# TopLevel.net
KiCad netlist of a schematic drawn in Altium Designer
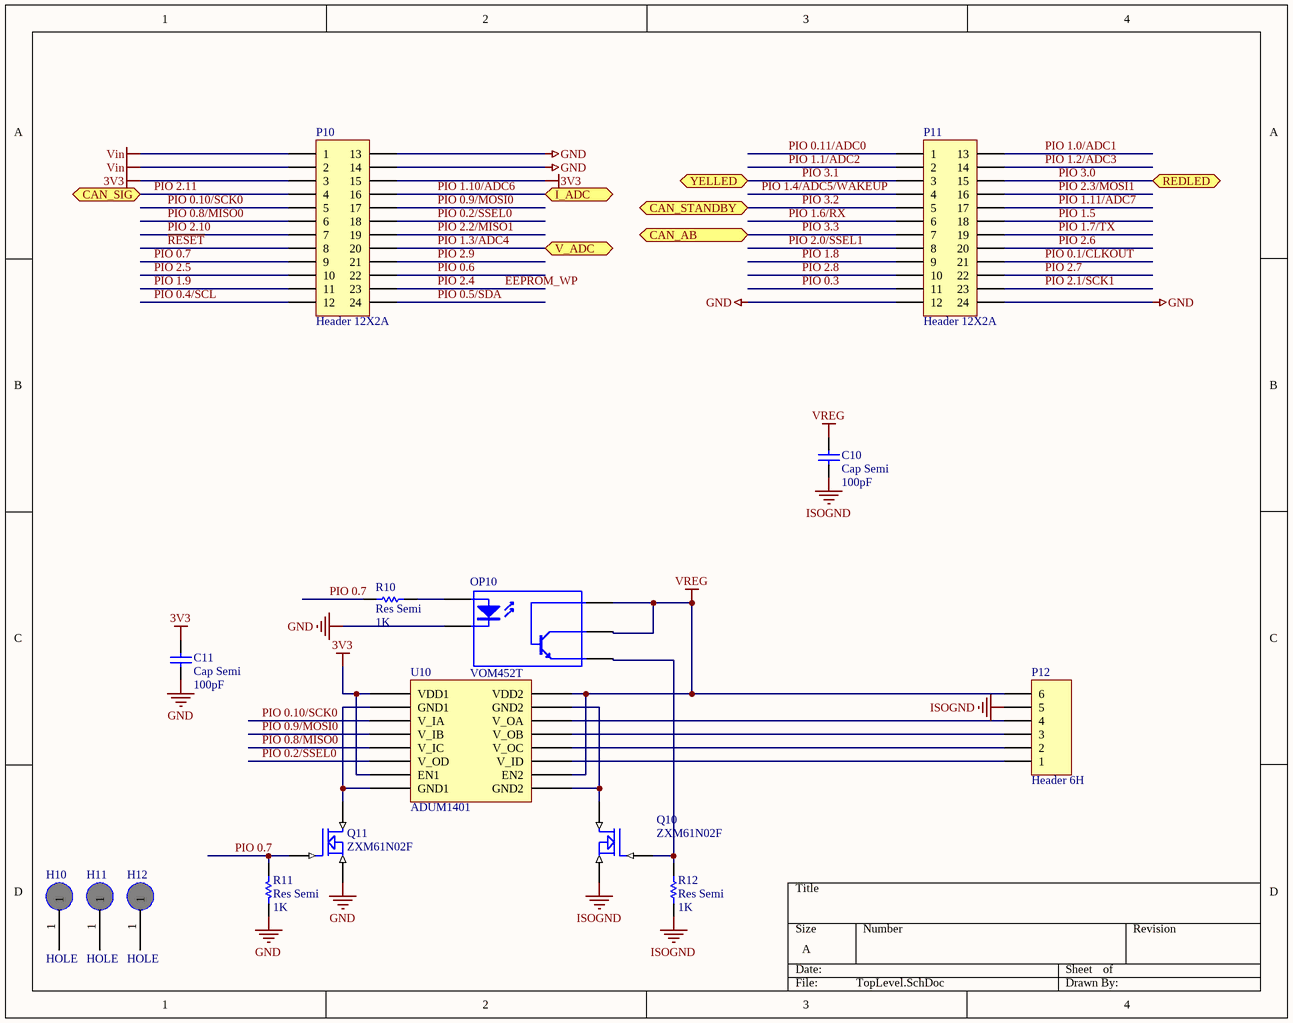
[diagram p0: TopLevel.SchDoc]

(export (version "E")
  (design (tool "Eeschema 10.0.6"))
  (components
    (comp (ref "C10")
      (value "Cap Semi")
      (footprint "1608[0603]")
      (description "Capacitor (Semiconductor SIM Model)")
      (fields (field (name "ALTIUM_VALUE") "100pF") (field (name "PUBLISHER") "Altium Limited"))
      (libsource (lib "Miscellaneous Devices") (part "Cap Semi"))
    )
    (comp (ref "C11")
      (value "Cap Semi")
      (footprint "1608[0603]")
      (description "Capacitor (Semiconductor SIM Model)")
      (fields (field (name "ALTIUM_VALUE") "100pF") (field (name "PUBLISHER") "Altium Limited"))
      (libsource (lib "Miscellaneous Devices") (part "Cap Semi"))
    )
    (comp (ref "H10")
      (value "HOLE")
      (footprint "M2.5")
      (description "Hole")
      (libsource (lib "Miscellaneous") (part "HOLE"))
    )
    (comp (ref "H11")
      (value "HOLE")
      (footprint "M2.5")
      (description "Hole")
      (libsource (lib "Miscellaneous") (part "HOLE"))
    )
    (comp (ref "H12")
      (value "HOLE")
      (footprint "M2.5")
      (description "Hole")
      (libsource (lib "Miscellaneous") (part "HOLE"))
    )
    (comp (ref "OP10") (value "VOM452T") (footprint "VOM452T") (libsource (lib "BMS") (part "VOM452T")))
    (comp (ref "P10")
      (value "Header 12X2A")
      (footprint "HDR2X12_CEN")
      (description "Header, 12-Pin, Dual row")
      (fields (field (name "PUBLISHER") "Altium Limited"))
      (libsource (lib "Miscellaneous Connectors") (part "Header 12X2A"))
    )
    (comp (ref "P11")
      (value "Header 12X2A")
      (footprint "HDR2X12_CEN")
      (description "Header, 12-Pin, Dual row")
      (fields (field (name "PUBLISHER") "Altium Limited"))
      (libsource (lib "Miscellaneous Connectors") (part "Header 12X2A"))
    )
    (comp (ref "P12")
      (value "Header 6H")
      (footprint "HDR1X6H")
      (description "Header, 6-Pin, Right Angle")
      (fields (field (name "PUBLISHER") "Altium Limited"))
      (libsource (lib "Miscellaneous Connectors") (part "Header 6H"))
    )
    (comp (ref "Q10")
      (value "ZXM61N02F")
      (footprint "SOT23-3")
      (description "1.7A, 20V N-Channel Enhancement mode FET")
      (libsource (lib "RCLDQ") (part "ZXM61N02F"))
    )
    (comp (ref "Q11")
      (value "ZXM61N02F")
      (footprint "SOT23-3")
      (description "1.7A, 20V N-Channel Enhancement mode FET")
      (libsource (lib "RCLDQ") (part "ZXM61N02F"))
    )
    (comp (ref "R10")
      (value "Res Semi")
      (footprint "0603")
      (description "Semiconductor Resistor")
      (fields (field (name "ALTIUM_VALUE") "1K") (field (name "PUBLISHER") "Altium Limited"))
      (libsource (lib "Miscellaneous Devices") (part "Res Semi"))
    )
    (comp (ref "R11")
      (value "Res Semi")
      (footprint "0603")
      (description "Semiconductor Resistor")
      (fields (field (name "ALTIUM_VALUE") "1K") (field (name "PUBLISHER") "Altium Limited"))
      (libsource (lib "Miscellaneous Devices") (part "Res Semi"))
    )
    (comp (ref "R12")
      (value "Res Semi")
      (footprint "0603")
      (description "Semiconductor Resistor")
      (fields (field (name "ALTIUM_VALUE") "1K") (field (name "PUBLISHER") "Altium Limited"))
      (libsource (lib "Miscellaneous Devices") (part "Res Semi"))
    )
    (comp (ref "U10") (value "ADUM1401") (footprint "SOIC_16_wide") (libsource (lib "BMS") (part "ADUM1401")))
  )
  (nets
    (net (code "1") (name "/EEPROM_WP") (class "Default")
      (node (ref "P10") (pin "23") (pinfunction "23_23") (pintype "passive"))
    )
    (net (code "2") (name "/PIO 0.1{slash}CLKOUT") (class "Default")
      (node (ref "P11") (pin "21") (pinfunction "21_21") (pintype "passive"))
    )
    (net (code "3") (name "/PIO 0.2{slash}SSEL0") (class "Default")
      (node (ref "P10") (pin "18") (pinfunction "18_18") (pintype "passive"))
      (node (ref "U10") (pin "6") (pinfunction "V_OD_6") (pintype "passive"))
    )
    (net (code "4") (name "/PIO 0.3") (class "Default")
      (node (ref "P11") (pin "11") (pinfunction "11_11") (pintype "passive"))
    )
    (net (code "5") (name "/PIO 0.4{slash}SCL") (class "Default")
      (node (ref "P10") (pin "12") (pinfunction "12_12") (pintype "passive"))
    )
    (net (code "6") (name "/PIO 0.5{slash}SDA") (class "Default")
      (node (ref "P10") (pin "24") (pinfunction "24_24") (pintype "passive"))
    )
    (net (code "7") (name "/PIO 0.6") (class "Default")
      (node (ref "P10") (pin "22") (pinfunction "22_22") (pintype "passive"))
    )
    (net (code "8") (name "/PIO 0.7") (class "Default")
      (node (ref "P10") (pin "9") (pinfunction "9_9") (pintype "passive"))
      (node (ref "Q11") (pin "1") (pinfunction "G_1") (pintype "input"))
      (node (ref "R10") (pin "2") (pinfunction "2_2") (pintype "passive"))
      (node (ref "R11") (pin "2") (pinfunction "2_2") (pintype "passive"))
    )
    (net (code "9") (name "/PIO 0.8{slash}MISO0") (class "Default")
      (node (ref "P10") (pin "6") (pinfunction "6_6") (pintype "passive"))
      (node (ref "U10") (pin "5") (pinfunction "V_IC_5") (pintype "passive"))
    )
    (net (code "10") (name "/PIO 0.9{slash}MOSI0") (class "Default")
      (node (ref "P10") (pin "17") (pinfunction "17_17") (pintype "passive"))
      (node (ref "U10") (pin "4") (pinfunction "V_IB_4") (pintype "passive"))
    )
    (net (code "11") (name "/PIO 0.10{slash}SCK0") (class "Default")
      (node (ref "P10") (pin "5") (pinfunction "5_5") (pintype "passive"))
      (node (ref "U10") (pin "3") (pinfunction "V_IA_3") (pintype "passive"))
    )
    (net (code "12") (name "/PIO 0.11{slash}ADC0") (class "Default")
      (node (ref "P11") (pin "1") (pinfunction "1_1") (pintype "passive"))
    )
    (net (code "13") (name "/PIO 1.0{slash}ADC1") (class "Default")
      (node (ref "P11") (pin "13") (pinfunction "13_13") (pintype "passive"))
    )
    (net (code "14") (name "/PIO 1.1{slash}ADC2") (class "Default")
      (node (ref "P11") (pin "2") (pinfunction "2_2") (pintype "passive"))
    )
    (net (code "15") (name "/PIO 1.2{slash}ADC3") (class "Default")
      (node (ref "P11") (pin "14") (pinfunction "14_14") (pintype "passive"))
    )
    (net (code "16") (name "/PIO 1.3{slash}ADC4") (class "Default")
      (node (ref "P10") (pin "20") (pinfunction "20_20") (pintype "passive"))
    )
    (net (code "17") (name "/PIO 1.4{slash}ADC5{slash}WAKEUP") (class "Default")
      (node (ref "P11") (pin "4") (pinfunction "4_4") (pintype "passive"))
    )
    (net (code "18") (name "/PIO 1.5") (class "Default")
      (node (ref "P11") (pin "18") (pinfunction "18_18") (pintype "passive"))
    )
    (net (code "19") (name "/PIO 1.6{slash}RX") (class "Default")
      (node (ref "P11") (pin "6") (pinfunction "6_6") (pintype "passive"))
    )
    (net (code "20") (name "/PIO 1.7{slash}TX") (class "Default")
      (node (ref "P11") (pin "19") (pinfunction "19_19") (pintype "passive"))
    )
    (net (code "21") (name "/PIO 1.8") (class "Default")
      (node (ref "P11") (pin "9") (pinfunction "9_9") (pintype "passive"))
    )
    (net (code "22") (name "/PIO 1.9") (class "Default")
      (node (ref "P10") (pin "11") (pinfunction "11_11") (pintype "passive"))
    )
    (net (code "23") (name "/PIO 1.10{slash}ADC6") (class "Default")
      (node (ref "P10") (pin "16") (pinfunction "16_16") (pintype "passive"))
    )
    (net (code "24") (name "/PIO 1.11{slash}ADC7") (class "Default")
      (node (ref "P11") (pin "17") (pinfunction "17_17") (pintype "passive"))
    )
    (net (code "25") (name "/PIO 2.0{slash}SSEL1") (class "Default")
      (node (ref "P11") (pin "8") (pinfunction "8_8") (pintype "passive"))
    )
    (net (code "26") (name "/PIO 2.1{slash}SCK1") (class "Default")
      (node (ref "P11") (pin "23") (pinfunction "23_23") (pintype "passive"))
    )
    (net (code "27") (name "/PIO 2.2{slash}MISO1") (class "Default")
      (node (ref "P10") (pin "19") (pinfunction "19_19") (pintype "passive"))
    )
    (net (code "28") (name "/PIO 2.3{slash}MOSI1") (class "Default")
      (node (ref "P11") (pin "16") (pinfunction "16_16") (pintype "passive"))
    )
    (net (code "29") (name "/PIO 2.5") (class "Default")
      (node (ref "P10") (pin "10") (pinfunction "10_10") (pintype "passive"))
    )
    (net (code "30") (name "/PIO 2.6") (class "Default")
      (node (ref "P11") (pin "20") (pinfunction "20_20") (pintype "passive"))
    )
    (net (code "31") (name "/PIO 2.7") (class "Default")
      (node (ref "P11") (pin "22") (pinfunction "22_22") (pintype "passive"))
    )
    (net (code "32") (name "/PIO 2.8") (class "Default")
      (node (ref "P11") (pin "10") (pinfunction "10_10") (pintype "passive"))
    )
    (net (code "33") (name "/PIO 2.9") (class "Default")
      (node (ref "P10") (pin "21") (pinfunction "21_21") (pintype "passive"))
    )
    (net (code "34") (name "/PIO 2.10") (class "Default")
      (node (ref "P10") (pin "7") (pinfunction "7_7") (pintype "passive"))
    )
    (net (code "35") (name "/PIO 2.11") (class "Default")
      (node (ref "P10") (pin "4") (pinfunction "4_4") (pintype "passive"))
    )
    (net (code "36") (name "/PIO 3.0") (class "Default")
      (node (ref "P11") (pin "15") (pinfunction "15_15") (pintype "passive"))
    )
    (net (code "37") (name "/PIO 3.1") (class "Default")
      (node (ref "P11") (pin "3") (pinfunction "3_3") (pintype "passive"))
    )
    (net (code "38") (name "/PIO 3.2") (class "Default")
      (node (ref "P11") (pin "5") (pinfunction "5_5") (pintype "passive"))
    )
    (net (code "39") (name "/PIO 3.3") (class "Default")
      (node (ref "P11") (pin "7") (pinfunction "7_7") (pintype "passive"))
    )
    (net (code "40") (name "/~{RESET}") (class "Default")
      (node (ref "P10") (pin "8") (pinfunction "8_8") (pintype "passive"))
    )
    (net (code "41") (name "3V3") (class "Default")
      (node (ref "C11") (pin "2") (pinfunction "2_2") (pintype "passive"))
      (node (ref "P10") (pin "15") (pinfunction "15_15") (pintype "passive"))
      (node (ref "P10") (pin "3") (pinfunction "3_3") (pintype "passive"))
      (node (ref "U10") (pin "1") (pinfunction "VDD1_1") (pintype "passive"))
      (node (ref "U10") (pin "7") (pinfunction "EN1_7") (pintype "passive"))
    )
    (net (code "42") (name "GND") (class "Default")
      (node (ref "C11") (pin "1") (pinfunction "1_1") (pintype "passive"))
      (node (ref "OP10") (pin "3") (pinfunction "K_3") (pintype "passive"))
      (node (ref "P10") (pin "13") (pinfunction "13_13") (pintype "passive"))
      (node (ref "P10") (pin "14") (pinfunction "14_14") (pintype "passive"))
      (node (ref "P11") (pin "12") (pinfunction "12_12") (pintype "passive"))
      (node (ref "P11") (pin "24") (pinfunction "24_24") (pintype "passive"))
      (node (ref "Q11") (pin "2") (pinfunction "S_2") (pintype "input"))
      (node (ref "R11") (pin "1") (pinfunction "1_1") (pintype "passive"))
    )
    (net (code "43") (name "ISOGND") (class "Default")
      (node (ref "C10") (pin "1") (pinfunction "1_1") (pintype "passive"))
      (node (ref "P12") (pin "5") (pinfunction "5_5") (pintype "passive"))
      (node (ref "Q10") (pin "2") (pinfunction "S_2") (pintype "input"))
      (node (ref "R12") (pin "1") (pinfunction "1_1") (pintype "passive"))
    )
    (net (code "44") (name "Net-(OP10-A)") (class "Default")
      (node (ref "OP10") (pin "1") (pinfunction "A_1") (pintype "passive"))
      (node (ref "R10") (pin "1") (pinfunction "1_1") (pintype "passive"))
    )
    (net (code "45") (name "Net-(OP10-E)") (class "Default")
      (node (ref "OP10") (pin "4") (pinfunction "E_4") (pintype "passive"))
      (node (ref "Q10") (pin "1") (pinfunction "G_1") (pintype "input"))
      (node (ref "R12") (pin "2") (pinfunction "2_2") (pintype "passive"))
    )
    (net (code "46") (name "Net-(Q10-D)") (class "Default")
      (node (ref "Q10") (pin "3") (pinfunction "D_3") (pintype "input"))
      (node (ref "U10") (pin "15") (pinfunction "GND2_15") (pintype "passive"))
      (node (ref "U10") (pin "9") (pinfunction "GND2_9") (pintype "passive"))
    )
    (net (code "47") (name "Net-(Q11-D)") (class "Default")
      (node (ref "Q11") (pin "3") (pinfunction "D_3") (pintype "input"))
      (node (ref "U10") (pin "2") (pinfunction "GND1_2") (pintype "passive"))
      (node (ref "U10") (pin "8") (pinfunction "GND1_8") (pintype "passive"))
    )
    (net (code "48") (name "Net-(U10-V_ID)") (class "Default")
      (node (ref "P12") (pin "1") (pinfunction "1_1") (pintype "passive"))
      (node (ref "U10") (pin "11") (pinfunction "V_ID_11") (pintype "passive"))
    )
    (net (code "49") (name "Net-(U10-V_OA)") (class "Default")
      (node (ref "P12") (pin "4") (pinfunction "4_4") (pintype "passive"))
      (node (ref "U10") (pin "14") (pinfunction "V_OA_14") (pintype "passive"))
    )
    (net (code "50") (name "Net-(U10-V_OB)") (class "Default")
      (node (ref "P12") (pin "3") (pinfunction "3_3") (pintype "passive"))
      (node (ref "U10") (pin "13") (pinfunction "V_OB_13") (pintype "passive"))
    )
    (net (code "51") (name "Net-(U10-V_OC)") (class "Default")
      (node (ref "P12") (pin "2") (pinfunction "2_2") (pintype "passive"))
      (node (ref "U10") (pin "12") (pinfunction "V_OC_12") (pintype "passive"))
    )
    (net (code "52") (name "VREG") (class "Default")
      (node (ref "C10") (pin "2") (pinfunction "2_2") (pintype "passive"))
      (node (ref "OP10") (pin "5") (pinfunction "C_5") (pintype "passive"))
      (node (ref "OP10") (pin "6") (pinfunction "C_6") (pintype "passive"))
      (node (ref "P12") (pin "6") (pinfunction "6_6") (pintype "passive"))
      (node (ref "U10") (pin "10") (pinfunction "EN2_10") (pintype "passive"))
      (node (ref "U10") (pin "16") (pinfunction "VDD2_16") (pintype "passive"))
    )
    (net (code "53") (name "Vin") (class "Default")
      (node (ref "P10") (pin "1") (pinfunction "1_1") (pintype "passive"))
      (node (ref "P10") (pin "2") (pinfunction "2_2") (pintype "passive"))
    )
    (net (code "54") (name "unconnected-(H10-Pad1)") (class "Default")
      (node (ref "H10") (pin "1") (pinfunction "1_1") (pintype "passive"))
    )
    (net (code "55") (name "unconnected-(H11-Pad1)") (class "Default")
      (node (ref "H11") (pin "1") (pinfunction "1_1") (pintype "passive"))
    )
    (net (code "56") (name "unconnected-(H12-Pad1)") (class "Default")
      (node (ref "H12") (pin "1") (pinfunction "1_1") (pintype "passive"))
    )
  )
)
